# Top.net
KiCad netlist of a schematic drawn in Altium Designer
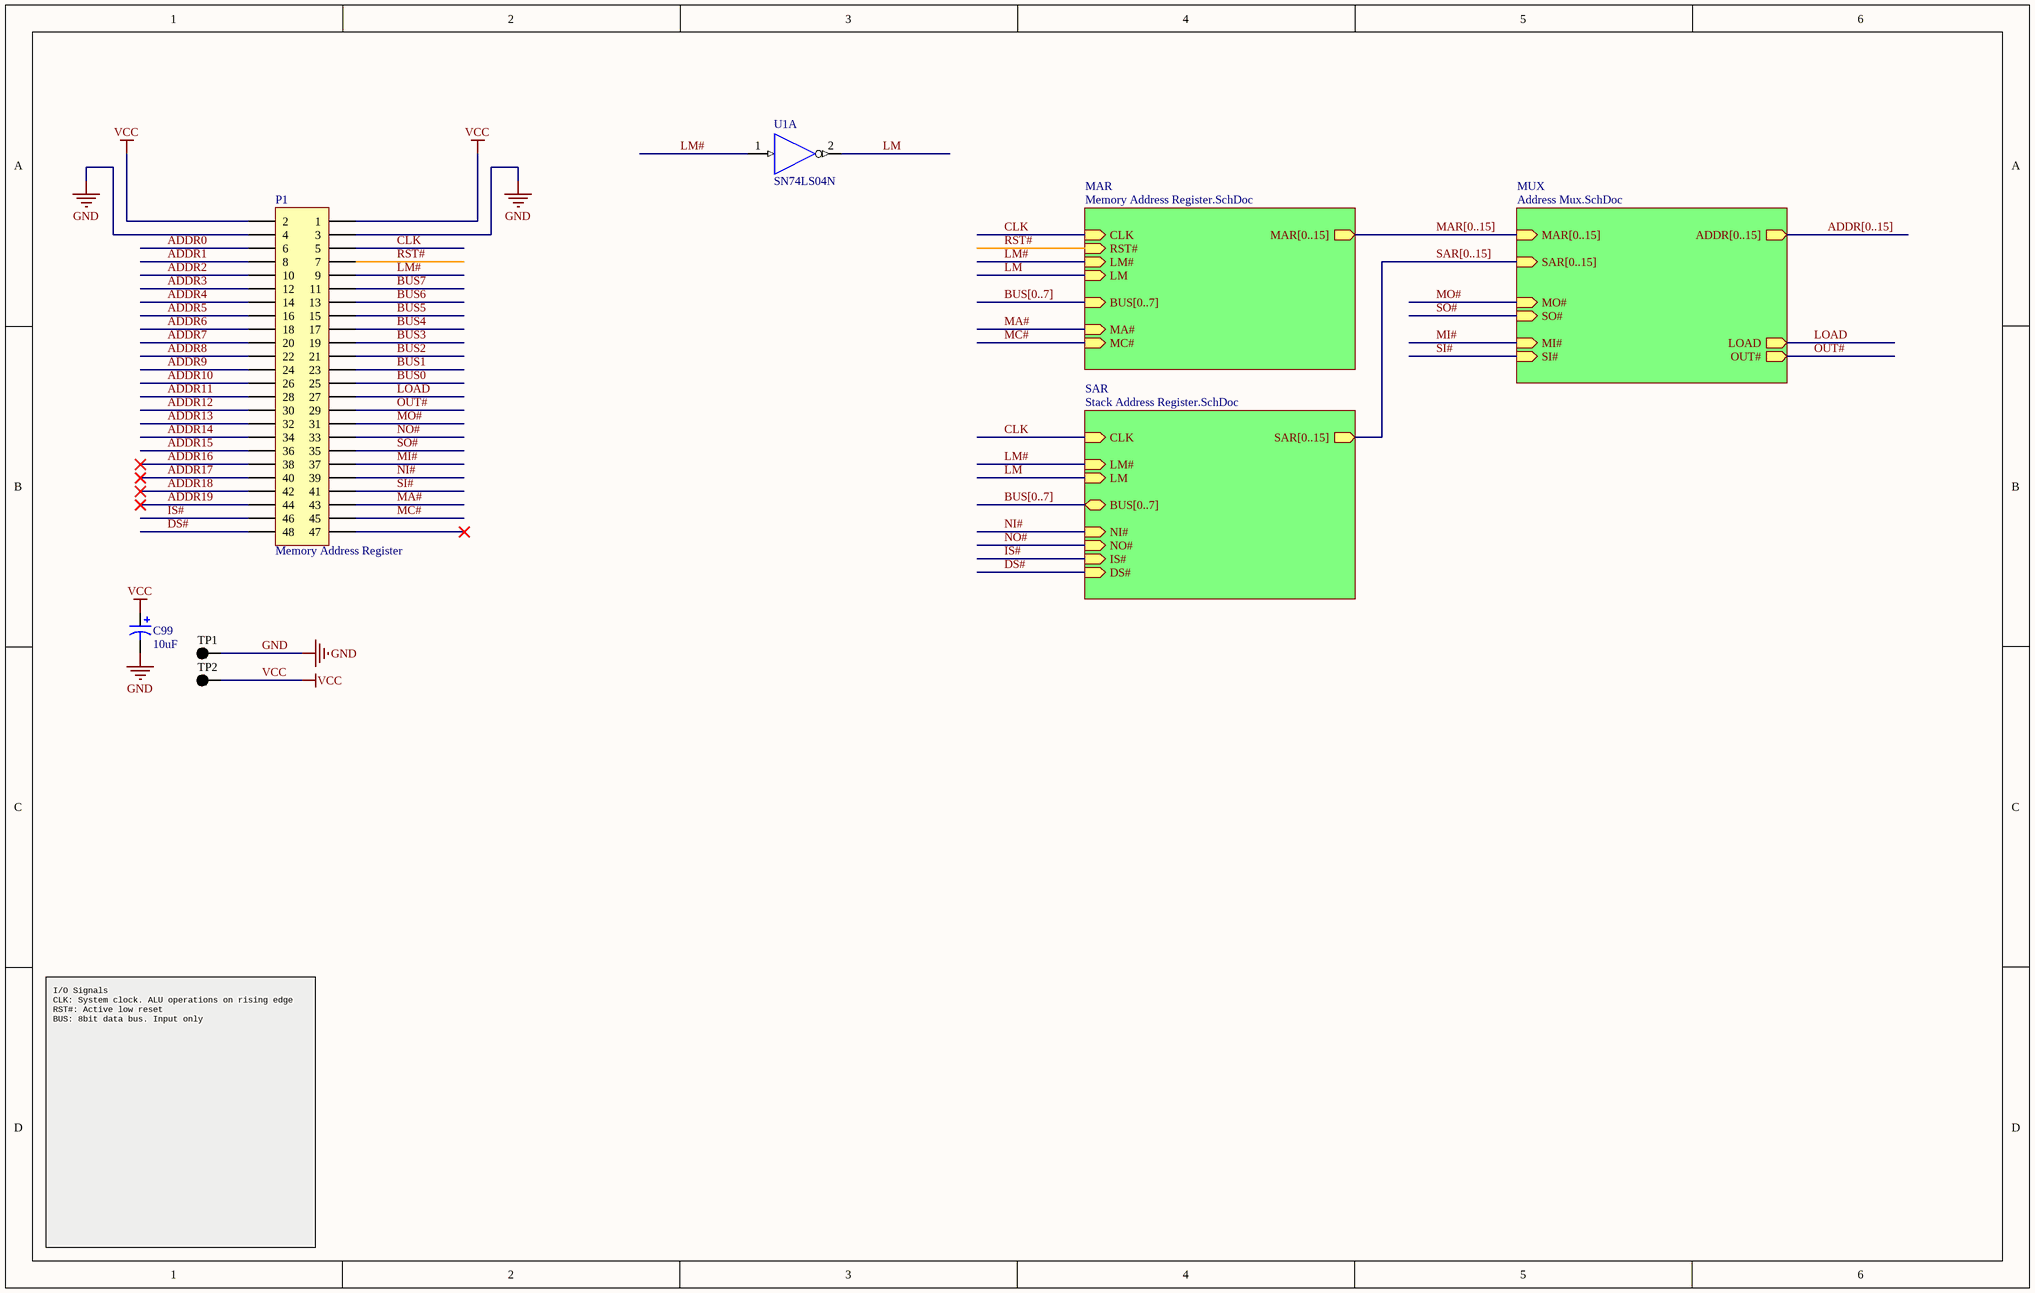
[diagram p0: Top.SchDoc]

(export (version "E")
  (design (tool "Eeschema 10.0.6"))
  (components
    (comp (ref "C99")
      (value "10uF")
      (footprint "C5x7")
      (description "Polarized Capacitor")
      (fields (field (name "Comment") "Cap Pol5") (field (name "PUBLISHER") "Altium Limited"))
      (libsource (lib "Miscellaneous Devices") (part "Cap Pol5"))
    )
    (comp (ref "P1")
      (value "Memory Address Register")
      (footprint "HDR2X24H")
      (description "Header, 24-Pin, Dual row, Right Angle")
      (fields (field (name "PUBLISHER") "Altium Limited"))
      (libsource (lib "Miscellaneous Connectors") (part "Header 24X2H"))
    )
    (comp (ref "TP1")
      (value "~")
      (footprint "KSTN-5011_V")
      (description "Test Point, Black, Through Hole, RoHS, Bulk")
      (fields (field (name "MANUFACTURER") "Keystone"))
      (libsource (lib "Altium Content Vault") (part "TESTPOINT_BLACK"))
    )
    (comp (ref "TP2")
      (value "~")
      (footprint "KSTN-5011_V")
      (description "Test Point, Black, Through Hole, RoHS, Bulk")
      (fields (field (name "MANUFACTURER") "Keystone"))
      (libsource (lib "Altium Content Vault") (part "TESTPOINT_BLACK"))
    )
    (comp (ref "U1")
      (value "SN74LS04N")
      (footprint "N014")
      (description "Hex Inverter")
      (fields (field (name "PUBLISHER") "Altium Limited"))
      (libsource (lib "TI Logic Gate 2") (part "SN74LS04N"))
    )
  )
  (nets
    (net (code "33") (name "/ADDR0") (class "Default")
      (node (ref "P1") (pin "6") (pinfunction "6_6") (pintype "passive"))
    )
    (net (code "34") (name "/ADDR1") (class "Default")
      (node (ref "P1") (pin "8") (pinfunction "8_8") (pintype "passive"))
    )
    (net (code "35") (name "/ADDR2") (class "Default")
      (node (ref "P1") (pin "10") (pinfunction "10_10") (pintype "passive"))
    )
    (net (code "36") (name "/ADDR3") (class "Default")
      (node (ref "P1") (pin "12") (pinfunction "12_12") (pintype "passive"))
    )
    (net (code "37") (name "/ADDR4") (class "Default")
      (node (ref "P1") (pin "14") (pinfunction "14_14") (pintype "passive"))
    )
    (net (code "38") (name "/ADDR5") (class "Default")
      (node (ref "P1") (pin "16") (pinfunction "16_16") (pintype "passive"))
    )
    (net (code "39") (name "/ADDR6") (class "Default")
      (node (ref "P1") (pin "18") (pinfunction "18_18") (pintype "passive"))
    )
    (net (code "40") (name "/ADDR7") (class "Default")
      (node (ref "P1") (pin "20") (pinfunction "20_20") (pintype "passive"))
    )
    (net (code "41") (name "/ADDR8") (class "Default")
      (node (ref "P1") (pin "22") (pinfunction "22_22") (pintype "passive"))
    )
    (net (code "42") (name "/ADDR9") (class "Default")
      (node (ref "P1") (pin "24") (pinfunction "24_24") (pintype "passive"))
    )
    (net (code "43") (name "/ADDR10") (class "Default")
      (node (ref "P1") (pin "26") (pinfunction "26_26") (pintype "passive"))
    )
    (net (code "44") (name "/ADDR11") (class "Default")
      (node (ref "P1") (pin "28") (pinfunction "28_28") (pintype "passive"))
    )
    (net (code "45") (name "/ADDR12") (class "Default")
      (node (ref "P1") (pin "30") (pinfunction "30_30") (pintype "passive"))
    )
    (net (code "46") (name "/ADDR13") (class "Default")
      (node (ref "P1") (pin "32") (pinfunction "32_32") (pintype "passive"))
    )
    (net (code "47") (name "/ADDR14") (class "Default")
      (node (ref "P1") (pin "34") (pinfunction "34_34") (pintype "passive"))
    )
    (net (code "48") (name "/ADDR15") (class "Default")
      (node (ref "P1") (pin "36") (pinfunction "36_36") (pintype "passive"))
    )
    (net (code "49") (name "/ADDR16") (class "Default")
      (node (ref "P1") (pin "38") (pinfunction "38_38") (pintype "passive+no_connect"))
    )
    (net (code "50") (name "/ADDR17") (class "Default")
      (node (ref "P1") (pin "40") (pinfunction "40_40") (pintype "passive+no_connect"))
    )
    (net (code "51") (name "/ADDR18") (class "Default")
      (node (ref "P1") (pin "42") (pinfunction "42_42") (pintype "passive+no_connect"))
    )
    (net (code "52") (name "/ADDR19") (class "Default")
      (node (ref "P1") (pin "44") (pinfunction "44_44") (pintype "passive+no_connect"))
    )
    (net (code "54") (name "/BUS0") (class "Default")
      (node (ref "P1") (pin "25") (pinfunction "25_25") (pintype "passive"))
    )
    (net (code "55") (name "/BUS1") (class "Default")
      (node (ref "P1") (pin "23") (pinfunction "23_23") (pintype "passive"))
    )
    (net (code "56") (name "/BUS2") (class "Default")
      (node (ref "P1") (pin "21") (pinfunction "21_21") (pintype "passive"))
    )
    (net (code "57") (name "/BUS3") (class "Default")
      (node (ref "P1") (pin "19") (pinfunction "19_19") (pintype "passive"))
    )
    (net (code "58") (name "/BUS4") (class "Default")
      (node (ref "P1") (pin "17") (pinfunction "17_17") (pintype "passive"))
    )
    (net (code "59") (name "/BUS5") (class "Default")
      (node (ref "P1") (pin "15") (pinfunction "15_15") (pintype "passive"))
    )
    (net (code "60") (name "/BUS6") (class "Default")
      (node (ref "P1") (pin "13") (pinfunction "13_13") (pintype "passive"))
    )
    (net (code "61") (name "/BUS7") (class "Default")
      (node (ref "P1") (pin "11") (pinfunction "11_11") (pintype "passive"))
    )
    (net (code "63") (name "/CLK") (class "Default")
      (node (ref "P1") (pin "5") (pinfunction "5_5") (pintype "passive"))
    )
    (net (code "64") (name "/DS#") (class "Default")
      (node (ref "P1") (pin "48") (pinfunction "48_48") (pintype "passive"))
    )
    (net (code "65") (name "/IS#") (class "Default")
      (node (ref "P1") (pin "46") (pinfunction "46_46") (pintype "passive"))
    )
    (net (code "66") (name "/LM") (class "Default")
      (node (ref "U1") (pin "2") (pinfunction "Y_2") (pintype "output"))
    )
    (net (code "67") (name "/LM#") (class "Default")
      (node (ref "P1") (pin "9") (pinfunction "9_9") (pintype "passive"))
      (node (ref "U1") (pin "1") (pinfunction "A_1") (pintype "input"))
    )
    (net (code "68") (name "/LOAD") (class "Default")
      (node (ref "P1") (pin "27") (pinfunction "27_27") (pintype "passive"))
    )
    (net (code "69") (name "/MA#") (class "Default")
      (node (ref "P1") (pin "43") (pinfunction "43_43") (pintype "passive"))
    )
    (net (code "71") (name "/MC#") (class "Default")
      (node (ref "P1") (pin "45") (pinfunction "45_45") (pintype "passive"))
    )
    (net (code "72") (name "/MI#") (class "Default")
      (node (ref "P1") (pin "37") (pinfunction "37_37") (pintype "passive"))
    )
    (net (code "73") (name "/MO#") (class "Default")
      (node (ref "P1") (pin "31") (pinfunction "31_31") (pintype "passive"))
    )
    (net (code "74") (name "/NI#") (class "Default")
      (node (ref "P1") (pin "39") (pinfunction "39_39") (pintype "passive"))
    )
    (net (code "75") (name "/NO#") (class "Default")
      (node (ref "P1") (pin "33") (pinfunction "33_33") (pintype "passive"))
    )
    (net (code "76") (name "/OUT#") (class "Default")
      (node (ref "P1") (pin "29") (pinfunction "29_29") (pintype "passive"))
    )
    (net (code "77") (name "/RST#") (class "Default")
      (node (ref "P1") (pin "7") (pinfunction "7_7") (pintype "passive"))
    )
    (net (code "79") (name "/SI#") (class "Default")
      (node (ref "P1") (pin "41") (pinfunction "41_41") (pintype "passive"))
    )
    (net (code "80") (name "/SO#") (class "Default")
      (node (ref "P1") (pin "35") (pinfunction "35_35") (pintype "passive"))
    )
    (net (code "81") (name "GND") (class "Default")
      (node (ref "C99") (pin "2") (pinfunction "2_2") (pintype "passive"))
      (node (ref "P1") (pin "3") (pinfunction "3_3") (pintype "passive"))
      (node (ref "P1") (pin "4") (pinfunction "4_4") (pintype "passive"))
      (node (ref "TP1") (pin "1") (pinfunction "1_1") (pintype "passive"))
      (node (ref "U1") (pin "7") (pinfunction "GND_7") (pintype "power_in"))
    )
    (net (code "82") (name "VCC") (class "Default")
      (node (ref "C99") (pin "1") (pinfunction "1_1") (pintype "passive"))
      (node (ref "P1") (pin "1") (pinfunction "1_1") (pintype "passive"))
      (node (ref "P1") (pin "2") (pinfunction "2_2") (pintype "passive"))
      (node (ref "TP2") (pin "1") (pinfunction "1_1") (pintype "passive"))
      (node (ref "U1") (pin "14") (pinfunction "VCC_14") (pintype "power_in"))
    )
    (net (code "83") (name "unconnected-(P1-Pad47)") (class "Default")
      (node (ref "P1") (pin "47") (pinfunction "47_47") (pintype "passive+no_connect"))
    )
  )
)
